# rvms_hardware.net
KiCad netlist of a schematic drawn in EasyEDA
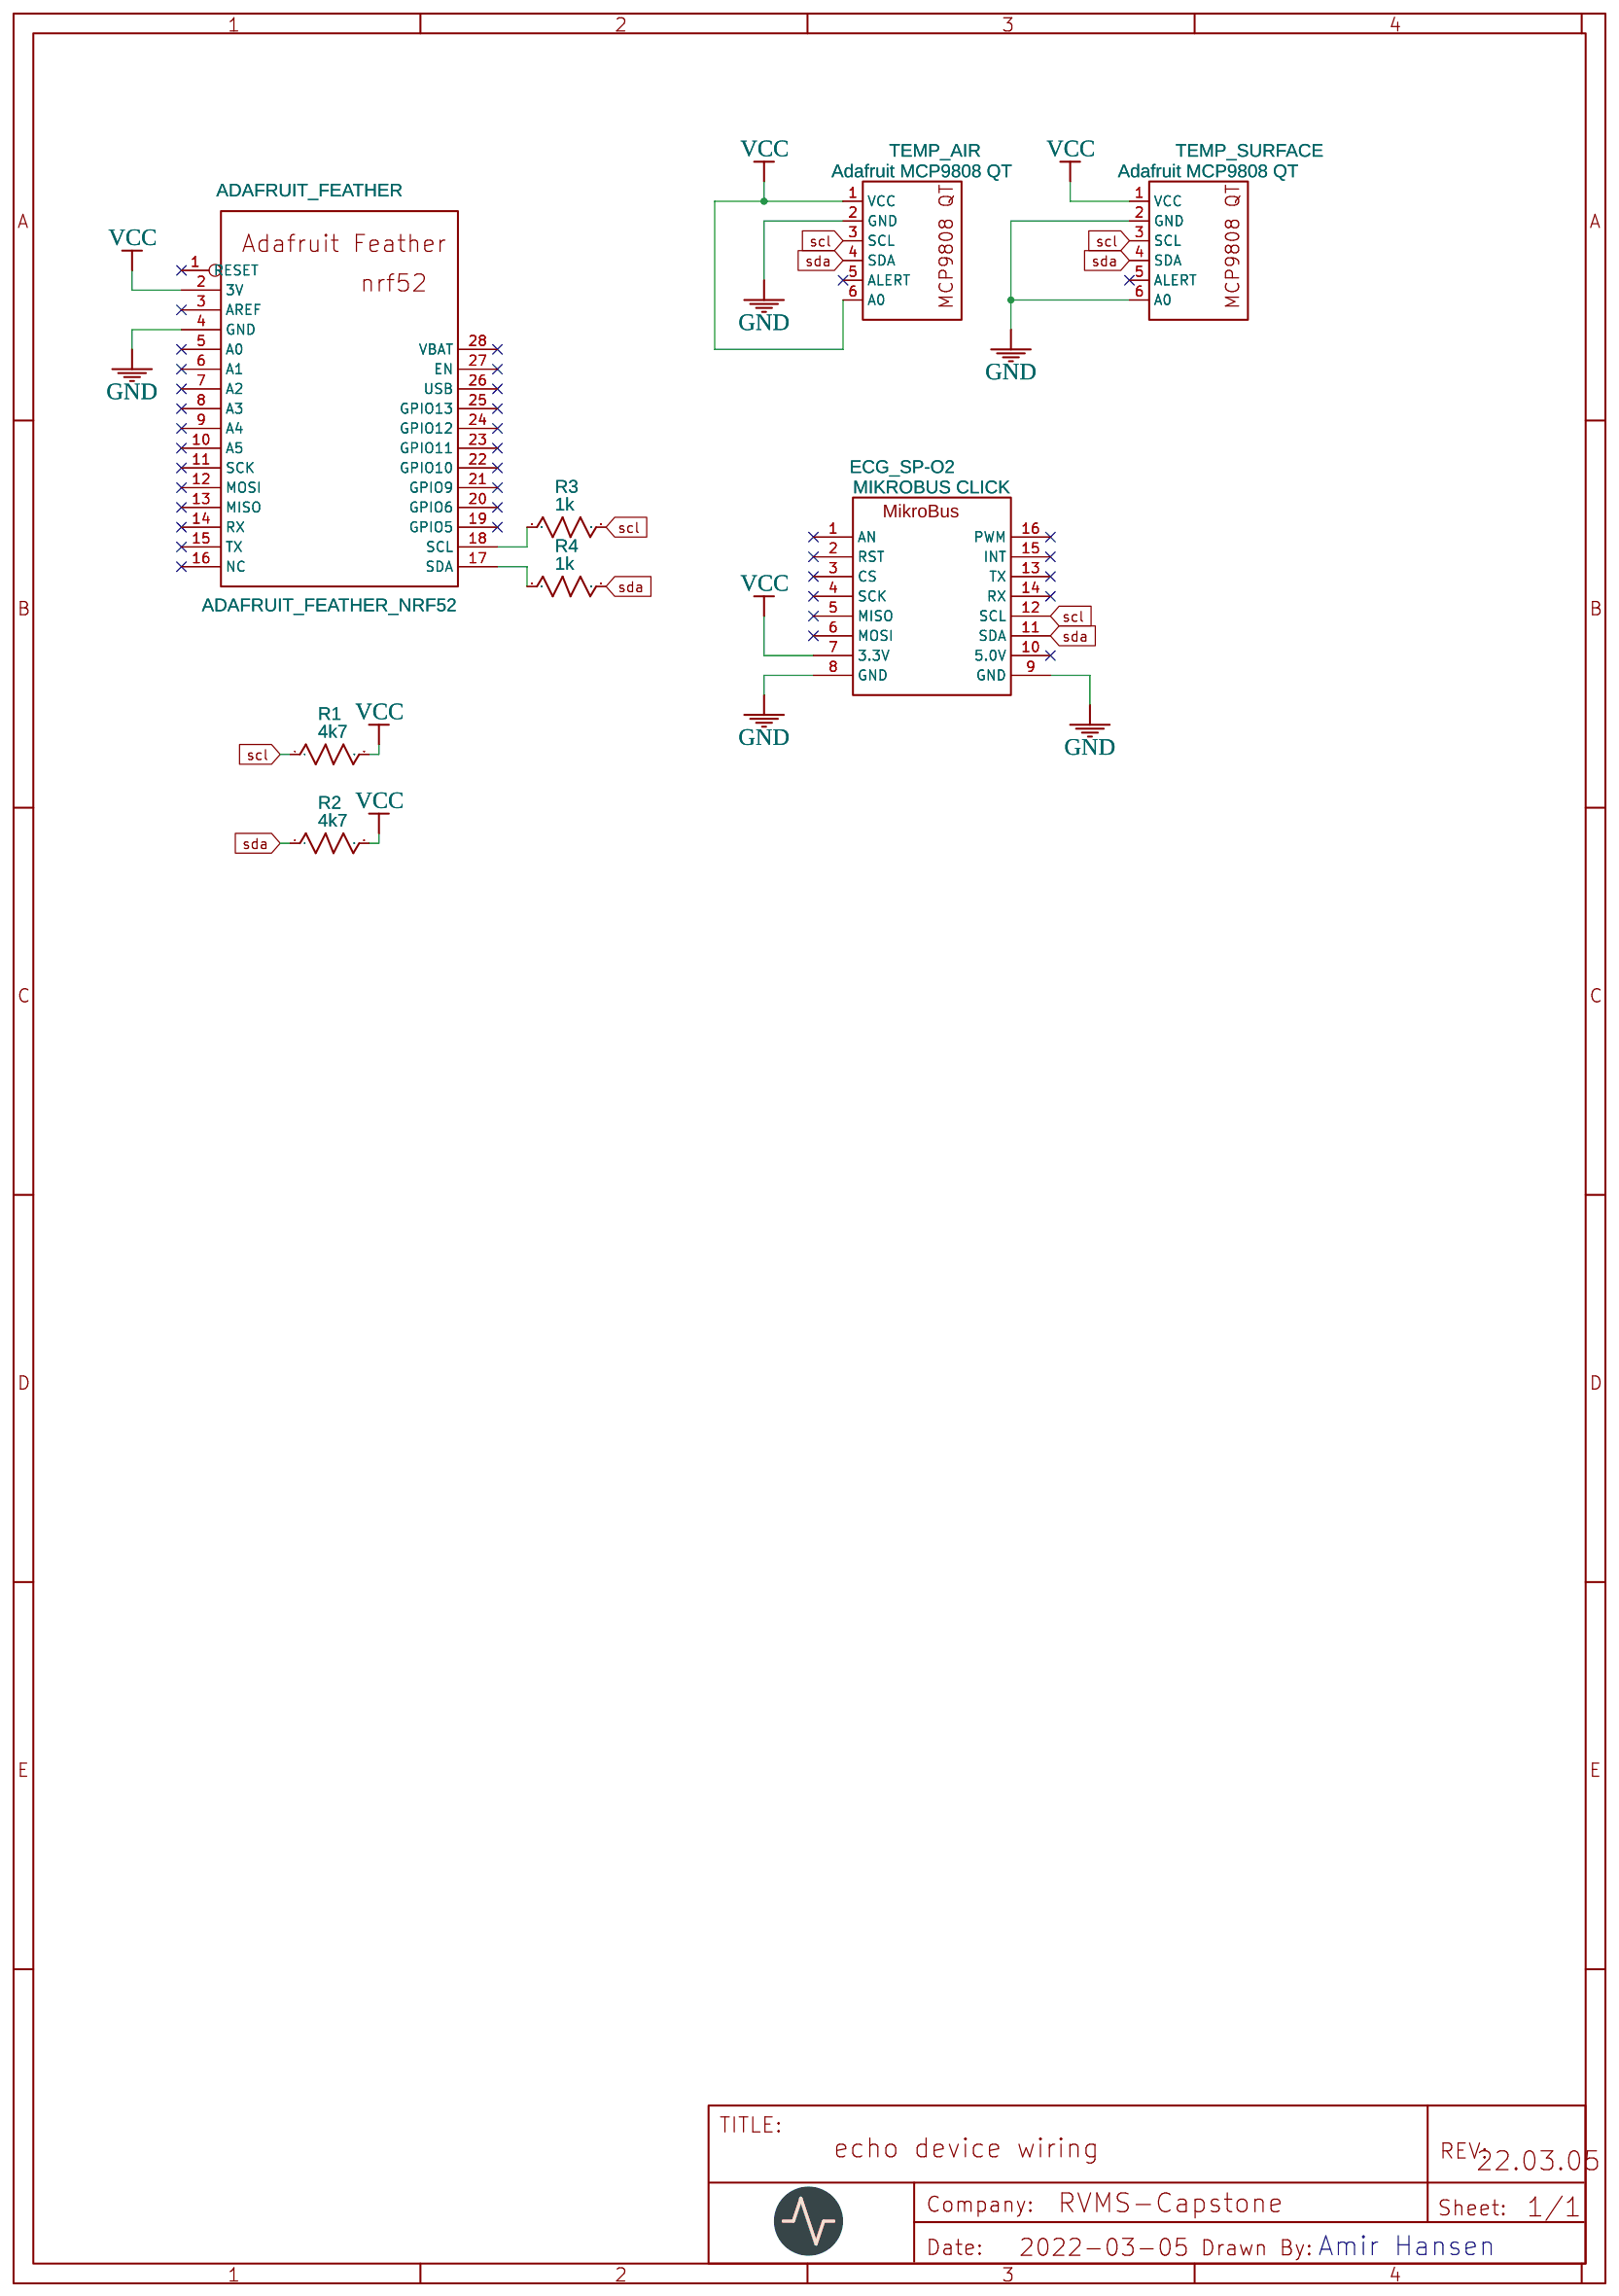
[diagram p0: schematic sheet]

(export (version "E")
  (design (tool "Eeschema 10.0.6"))
  (components
    (comp (ref "ADAFRUIT_FEATHER")
      (value "ADAFRUIT_FEATHER_NRF52")
      (libsource (lib "") (part "Adafruit Feather nrf52"))
    )
    (comp (ref "ECG_SP-O2") (value "MIKROBUS CLICK") (libsource (lib "") (part "MIKROBUS CLICK")))
    (comp (ref "R1") (value "4k7") (libsource (lib "") (part "R_AXIAL-0.3_US")))
    (comp (ref "R2") (value "4k7") (libsource (lib "") (part "R_AXIAL-0.3_US")))
    (comp (ref "R3") (value "1k") (libsource (lib "") (part "R_AXIAL-0.3_US")))
    (comp (ref "R4") (value "1k") (libsource (lib "") (part "R_AXIAL-0.3_US")))
    (comp (ref "TEMP_AIR") (value "Adafruit MCP9808 QT") (libsource (lib "") (part "Adafruit MCP9808 QT")))
    (comp (ref "TEMP_SURFACE")
      (value "Adafruit MCP9808 QT")
      (libsource (lib "") (part "Adafruit MCP9808 QT_1"))
    )
  )
  (nets
    (net (code "1") (name "GND") (class "Default")
      (node (ref "ADAFRUIT_FEATHER") (pin "4") (pinfunction "GND_4") (pintype "unspecified"))
      (node (ref "ECG_SP-O2") (pin "8") (pinfunction "GND_8") (pintype "passive"))
      (node (ref "ECG_SP-O2") (pin "9") (pinfunction "GND_9") (pintype "passive"))
      (node (ref "TEMP_AIR") (pin "2") (pinfunction "GND_2") (pintype "passive"))
      (node (ref "TEMP_SURFACE") (pin "2") (pinfunction "GND_2") (pintype "passive"))
      (node (ref "TEMP_SURFACE") (pin "6") (pinfunction "A0_6") (pintype "unspecified"))
    )
    (net (code "2") (name "Net-(ADAFRUIT_FEATHER-SCL)") (class "Default")
      (node (ref "ADAFRUIT_FEATHER") (pin "18") (pinfunction "SCL_18") (pintype "unspecified"))
      (node (ref "R3") (pin "1") (pinfunction "1_1") (pintype "unspecified"))
    )
    (net (code "3") (name "Net-(ADAFRUIT_FEATHER-SDA)") (class "Default")
      (node (ref "ADAFRUIT_FEATHER") (pin "17") (pinfunction "SDA_17") (pintype "unspecified"))
      (node (ref "R4") (pin "1") (pinfunction "1_1") (pintype "unspecified"))
    )
    (net (code "4") (name "VCC") (class "Default")
      (node (ref "ADAFRUIT_FEATHER") (pin "2") (pinfunction "3V_2") (pintype "unspecified"))
      (node (ref "ECG_SP-O2") (pin "7") (pinfunction "3.3V_7") (pintype "passive"))
      (node (ref "R1") (pin "2") (pinfunction "2_2") (pintype "unspecified"))
      (node (ref "R2") (pin "2") (pinfunction "2_2") (pintype "unspecified"))
      (node (ref "TEMP_AIR") (pin "1") (pinfunction "VCC_1") (pintype "passive"))
      (node (ref "TEMP_AIR") (pin "6") (pinfunction "A0_6") (pintype "unspecified"))
      (node (ref "TEMP_SURFACE") (pin "1") (pinfunction "VCC_1") (pintype "passive"))
    )
    (net (code "5") (name "scl") (class "Default")
      (node (ref "ECG_SP-O2") (pin "12") (pinfunction "SCL_12") (pintype "unspecified"))
      (node (ref "R1") (pin "1") (pinfunction "1_1") (pintype "unspecified"))
      (node (ref "R3") (pin "2") (pinfunction "2_2") (pintype "unspecified"))
      (node (ref "TEMP_AIR") (pin "3") (pinfunction "SCL_3") (pintype "bidirectional"))
      (node (ref "TEMP_SURFACE") (pin "3") (pinfunction "SCL_3") (pintype "bidirectional"))
    )
    (net (code "6") (name "sda") (class "Default")
      (node (ref "ECG_SP-O2") (pin "11") (pinfunction "SDA_11") (pintype "unspecified"))
      (node (ref "R2") (pin "1") (pinfunction "1_1") (pintype "unspecified"))
      (node (ref "R4") (pin "2") (pinfunction "2_2") (pintype "unspecified"))
      (node (ref "TEMP_AIR") (pin "4") (pinfunction "SDA_4") (pintype "bidirectional"))
      (node (ref "TEMP_SURFACE") (pin "4") (pinfunction "SDA_4") (pintype "bidirectional"))
    )
    (net (code "7") (name "unconnected-(ADAFRUIT_FEATHER-A0-Pad5)") (class "Default")
      (node (ref "ADAFRUIT_FEATHER") (pin "5") (pinfunction "A0_5") (pintype "unspecified+no_connect"))
    )
    (net (code "8") (name "unconnected-(ADAFRUIT_FEATHER-A1-Pad6)") (class "Default")
      (node (ref "ADAFRUIT_FEATHER") (pin "6") (pinfunction "A1_6") (pintype "unspecified+no_connect"))
    )
    (net (code "9") (name "unconnected-(ADAFRUIT_FEATHER-A2-Pad7)") (class "Default")
      (node (ref "ADAFRUIT_FEATHER") (pin "7") (pinfunction "A2_7") (pintype "unspecified+no_connect"))
    )
    (net (code "10") (name "unconnected-(ADAFRUIT_FEATHER-A3-Pad8)") (class "Default")
      (node (ref "ADAFRUIT_FEATHER") (pin "8") (pinfunction "A3_8") (pintype "unspecified+no_connect"))
    )
    (net (code "11") (name "unconnected-(ADAFRUIT_FEATHER-A4-Pad9)") (class "Default")
      (node (ref "ADAFRUIT_FEATHER") (pin "9") (pinfunction "A4_9") (pintype "unspecified+no_connect"))
    )
    (net (code "12") (name "unconnected-(ADAFRUIT_FEATHER-A5-Pad10)") (class "Default")
      (node (ref "ADAFRUIT_FEATHER") (pin "10") (pinfunction "A5_10") (pintype "unspecified+no_connect"))
    )
    (net (code "13") (name "unconnected-(ADAFRUIT_FEATHER-AREF-Pad3)") (class "Default")
      (node (ref "ADAFRUIT_FEATHER") (pin "3") (pinfunction "AREF_3") (pintype "unspecified+no_connect"))
    )
    (net (code "14") (name "unconnected-(ADAFRUIT_FEATHER-EN-Pad27)") (class "Default")
      (node (ref "ADAFRUIT_FEATHER") (pin "27") (pinfunction "EN_27") (pintype "unspecified+no_connect"))
    )
    (net (code "15") (name "unconnected-(ADAFRUIT_FEATHER-GPIO5-Pad19)") (class "Default")
      (node (ref "ADAFRUIT_FEATHER") (pin "19") (pinfunction "GPIO5_19") (pintype "unspecified+no_connect"))
    )
    (net (code "16") (name "unconnected-(ADAFRUIT_FEATHER-GPIO6-Pad20)") (class "Default")
      (node (ref "ADAFRUIT_FEATHER") (pin "20") (pinfunction "GPIO6_20") (pintype "unspecified+no_connect"))
    )
    (net (code "17") (name "unconnected-(ADAFRUIT_FEATHER-GPIO9-Pad21)") (class "Default")
      (node (ref "ADAFRUIT_FEATHER") (pin "21") (pinfunction "GPIO9_21") (pintype "unspecified+no_connect"))
    )
    (net (code "18") (name "unconnected-(ADAFRUIT_FEATHER-GPIO10-Pad22)") (class "Default")
      (node (ref "ADAFRUIT_FEATHER") (pin "22") (pinfunction "GPIO10_22") (pintype "unspecified+no_connect"))
    )
    (net (code "19") (name "unconnected-(ADAFRUIT_FEATHER-GPIO11-Pad23)") (class "Default")
      (node (ref "ADAFRUIT_FEATHER") (pin "23") (pinfunction "GPIO11_23") (pintype "unspecified+no_connect"))
    )
    (net (code "20") (name "unconnected-(ADAFRUIT_FEATHER-GPIO12-Pad24)") (class "Default")
      (node (ref "ADAFRUIT_FEATHER") (pin "24") (pinfunction "GPIO12_24") (pintype "unspecified+no_connect"))
    )
    (net (code "21") (name "unconnected-(ADAFRUIT_FEATHER-GPIO13-Pad25)") (class "Default")
      (node (ref "ADAFRUIT_FEATHER") (pin "25") (pinfunction "GPIO13_25") (pintype "unspecified+no_connect"))
    )
    (net (code "22") (name "unconnected-(ADAFRUIT_FEATHER-MISO-Pad13)") (class "Default")
      (node (ref "ADAFRUIT_FEATHER") (pin "13") (pinfunction "MISO_13") (pintype "unspecified+no_connect"))
    )
    (net (code "23") (name "unconnected-(ADAFRUIT_FEATHER-MOSI-Pad12)") (class "Default")
      (node (ref "ADAFRUIT_FEATHER") (pin "12") (pinfunction "MOSI_12") (pintype "unspecified+no_connect"))
    )
    (net (code "24") (name "unconnected-(ADAFRUIT_FEATHER-NC-Pad16)") (class "Default")
      (node (ref "ADAFRUIT_FEATHER") (pin "16") (pinfunction "NC_16") (pintype "unspecified+no_connect"))
    )
    (net (code "25") (name "unconnected-(ADAFRUIT_FEATHER-RESET-Pad1)") (class "Default")
      (node (ref "ADAFRUIT_FEATHER") (pin "1") (pinfunction "RESET_1") (pintype "unspecified+no_connect"))
    )
    (net (code "26") (name "unconnected-(ADAFRUIT_FEATHER-RX-Pad14)") (class "Default")
      (node (ref "ADAFRUIT_FEATHER") (pin "14") (pinfunction "RX_14") (pintype "unspecified+no_connect"))
    )
    (net (code "27") (name "unconnected-(ADAFRUIT_FEATHER-SCK-Pad11)") (class "Default")
      (node (ref "ADAFRUIT_FEATHER") (pin "11") (pinfunction "SCK_11") (pintype "unspecified+no_connect"))
    )
    (net (code "28") (name "unconnected-(ADAFRUIT_FEATHER-TX-Pad15)") (class "Default")
      (node (ref "ADAFRUIT_FEATHER") (pin "15") (pinfunction "TX_15") (pintype "unspecified+no_connect"))
    )
    (net (code "29") (name "unconnected-(ADAFRUIT_FEATHER-USB-Pad26)") (class "Default")
      (node (ref "ADAFRUIT_FEATHER") (pin "26") (pinfunction "USB_26") (pintype "unspecified+no_connect"))
    )
    (net (code "30") (name "unconnected-(ADAFRUIT_FEATHER-VBAT-Pad28)") (class "Default")
      (node (ref "ADAFRUIT_FEATHER") (pin "28") (pinfunction "VBAT_28") (pintype "unspecified+no_connect"))
    )
    (net (code "31") (name "unconnected-(ECG_SP-O2-5.0V-Pad10)") (class "Default")
      (node (ref "ECG_SP-O2") (pin "10") (pinfunction "5.0V_10") (pintype "passive+no_connect"))
    )
    (net (code "32") (name "unconnected-(ECG_SP-O2-AN-Pad1)") (class "Default")
      (node (ref "ECG_SP-O2") (pin "1") (pinfunction "AN_1") (pintype "unspecified+no_connect"))
    )
    (net (code "33") (name "unconnected-(ECG_SP-O2-CS-Pad3)") (class "Default")
      (node (ref "ECG_SP-O2") (pin "3") (pinfunction "CS_3") (pintype "unspecified+no_connect"))
    )
    (net (code "34") (name "unconnected-(ECG_SP-O2-INT-Pad15)") (class "Default")
      (node (ref "ECG_SP-O2") (pin "15") (pinfunction "INT_15") (pintype "unspecified+no_connect"))
    )
    (net (code "35") (name "unconnected-(ECG_SP-O2-MISO-Pad5)") (class "Default")
      (node (ref "ECG_SP-O2") (pin "5") (pinfunction "MISO_5") (pintype "unspecified+no_connect"))
    )
    (net (code "36") (name "unconnected-(ECG_SP-O2-MOSI-Pad6)") (class "Default")
      (node (ref "ECG_SP-O2") (pin "6") (pinfunction "MOSI_6") (pintype "unspecified+no_connect"))
    )
    (net (code "37") (name "unconnected-(ECG_SP-O2-PWM-Pad16)") (class "Default")
      (node (ref "ECG_SP-O2") (pin "16") (pinfunction "PWM_16") (pintype "unspecified+no_connect"))
    )
    (net (code "38") (name "unconnected-(ECG_SP-O2-RST-Pad2)") (class "Default")
      (node (ref "ECG_SP-O2") (pin "2") (pinfunction "RST_2") (pintype "unspecified+no_connect"))
    )
    (net (code "39") (name "unconnected-(ECG_SP-O2-RX-Pad14)") (class "Default")
      (node (ref "ECG_SP-O2") (pin "14") (pinfunction "RX_14") (pintype "unspecified+no_connect"))
    )
    (net (code "40") (name "unconnected-(ECG_SP-O2-SCK-Pad4)") (class "Default")
      (node (ref "ECG_SP-O2") (pin "4") (pinfunction "SCK_4") (pintype "unspecified+no_connect"))
    )
    (net (code "41") (name "unconnected-(ECG_SP-O2-TX-Pad13)") (class "Default")
      (node (ref "ECG_SP-O2") (pin "13") (pinfunction "TX_13") (pintype "unspecified+no_connect"))
    )
    (net (code "42") (name "unconnected-(TEMP_AIR-ALERT-Pad5)") (class "Default")
      (node (ref "TEMP_AIR") (pin "5") (pinfunction "ALERT_5") (pintype "unspecified+no_connect"))
    )
    (net (code "43") (name "unconnected-(TEMP_SURFACE-ALERT-Pad5)") (class "Default")
      (node (ref "TEMP_SURFACE") (pin "5") (pinfunction "ALERT_5") (pintype "unspecified+no_connect"))
    )
  )
)
